# as14120_fpga_cypress.net
KiCad netlist of a schematic drawn in Altium Designer
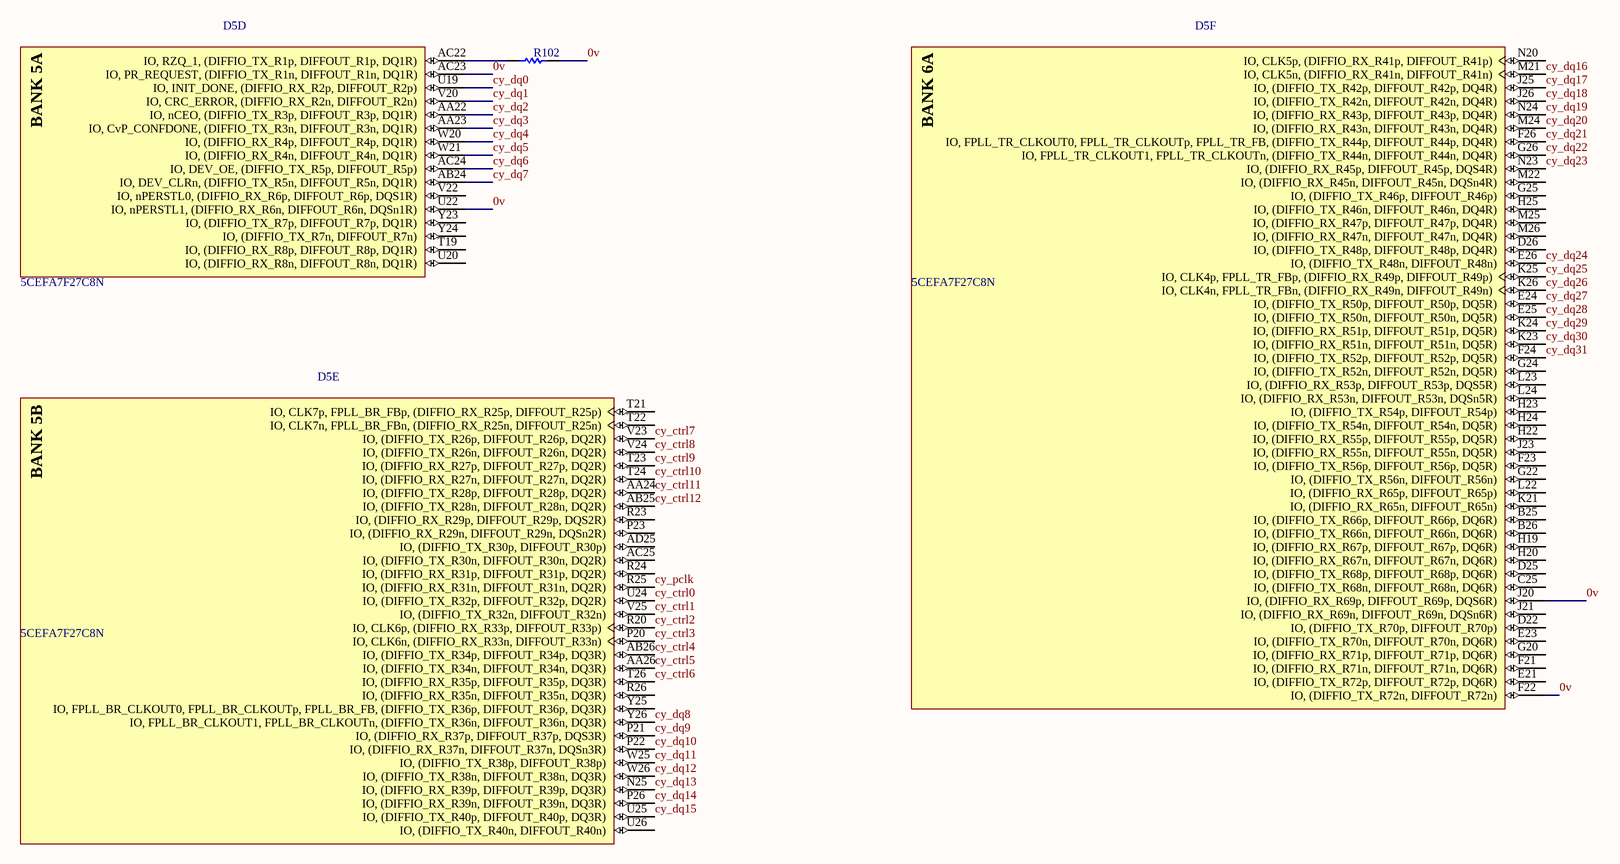
[diagram p0: as14120_fpga_cypress.SchDoc]

(export (version "E")
  (design (tool "Eeschema 10.0.6"))
  (components
    (comp (ref "D5")
      (value "5CEFA7F27C8N")
      (footprint "ALTR-672-FBGA-2000A")
      (fields (field (name "MANUFACTURER") "Altera"))
      (libsource (lib "Altera Cyclone V E") (part "5CEFA7F27C8N"))
    )
    (comp (ref "R102")
      (value "???")
      (footprint "RESC0603(1608)_L")
      (description "1K 0.1W 5% 0603 (1608 Metric)  SMD")
      (fields (field (name "TOLERANCE") "5 %") (field (name "POWER") "0.1 W"))
      (libsource (lib "as14120") (part "RES_0603"))
    )
  )
  (nets
    (net (code "1") (name "/0v") (class "Default")
      (node (ref "D5") (pin "AC23") (pinfunction "IO,_PR_REQUEST,_(DIFFIO_TX_R1n,_DIFFOUT_R1n,_DQ1R)_AC23") (pintype "bidirectional"))
      (node (ref "D5") (pin "F22") (pinfunction "IO,_(DIFFIO_TX_R72n,_DIFFOUT_R72n)_F22") (pintype "bidirectional"))
      (node (ref "D5") (pin "J20") (pinfunction "IO,_(DIFFIO_RX_R69p,_DIFFOUT_R69p,_DQS6R)_J20") (pintype "bidirectional"))
      (node (ref "D5") (pin "U22") (pinfunction "IO,_nPERSTL1,_(DIFFIO_RX_R6n,_DIFFOUT_R6n,_DQSn1R)_U22") (pintype "bidirectional"))
      (node (ref "R102") (pin "2") (pinfunction "2_2") (pintype "passive"))
    )
    (net (code "2") (name "/cy_ctrl0") (class "Default")
      (node (ref "D5") (pin "U24") (pinfunction "IO,_(DIFFIO_TX_R32p,_DIFFOUT_R32p,_DQ2R)_U24") (pintype "bidirectional"))
    )
    (net (code "3") (name "/cy_ctrl1") (class "Default")
      (node (ref "D5") (pin "V25") (pinfunction "IO,_(DIFFIO_TX_R32n,_DIFFOUT_R32n)_V25") (pintype "bidirectional"))
    )
    (net (code "4") (name "/cy_ctrl2") (class "Default")
      (node (ref "D5") (pin "R20") (pinfunction "IO,_CLK6p,_(DIFFIO_RX_R33p,_DIFFOUT_R33p)_R20") (pintype "bidirectional"))
    )
    (net (code "5") (name "/cy_ctrl3") (class "Default")
      (node (ref "D5") (pin "P20") (pinfunction "IO,_CLK6n,_(DIFFIO_RX_R33n,_DIFFOUT_R33n)_P20") (pintype "bidirectional"))
    )
    (net (code "6") (name "/cy_ctrl4") (class "Default")
      (node (ref "D5") (pin "AB26") (pinfunction "IO,_(DIFFIO_TX_R34p,_DIFFOUT_R34p,_DQ3R)_AB26") (pintype "bidirectional"))
    )
    (net (code "7") (name "/cy_ctrl5") (class "Default")
      (node (ref "D5") (pin "AA26") (pinfunction "IO,_(DIFFIO_TX_R34n,_DIFFOUT_R34n,_DQ3R)_AA26") (pintype "bidirectional"))
    )
    (net (code "8") (name "/cy_ctrl6") (class "Default")
      (node (ref "D5") (pin "T26") (pinfunction "IO,_(DIFFIO_RX_R35p,_DIFFOUT_R35p,_DQ3R)_T26") (pintype "bidirectional"))
    )
    (net (code "9") (name "/cy_ctrl7") (class "Default")
      (node (ref "D5") (pin "V23") (pinfunction "IO,_(DIFFIO_TX_R26p,_DIFFOUT_R26p,_DQ2R)_V23") (pintype "bidirectional"))
    )
    (net (code "10") (name "/cy_ctrl8") (class "Default")
      (node (ref "D5") (pin "V24") (pinfunction "IO,_(DIFFIO_TX_R26n,_DIFFOUT_R26n,_DQ2R)_V24") (pintype "bidirectional"))
    )
    (net (code "11") (name "/cy_ctrl9") (class "Default")
      (node (ref "D5") (pin "T23") (pinfunction "IO,_(DIFFIO_RX_R27p,_DIFFOUT_R27p,_DQ2R)_T23") (pintype "bidirectional"))
    )
    (net (code "12") (name "/cy_ctrl10") (class "Default")
      (node (ref "D5") (pin "T24") (pinfunction "IO,_(DIFFIO_RX_R27n,_DIFFOUT_R27n,_DQ2R)_T24") (pintype "bidirectional"))
    )
    (net (code "13") (name "/cy_ctrl11") (class "Default")
      (node (ref "D5") (pin "AA24") (pinfunction "IO,_(DIFFIO_TX_R28p,_DIFFOUT_R28p,_DQ2R)_AA24") (pintype "bidirectional"))
    )
    (net (code "14") (name "/cy_ctrl12") (class "Default")
      (node (ref "D5") (pin "AB25") (pinfunction "IO,_(DIFFIO_TX_R28n,_DIFFOUT_R28n,_DQ2R)_AB25") (pintype "bidirectional"))
    )
    (net (code "15") (name "/cy_dq0") (class "Default")
      (node (ref "D5") (pin "U19") (pinfunction "IO,_INIT_DONE,_(DIFFIO_RX_R2p,_DIFFOUT_R2p)_U19") (pintype "bidirectional"))
    )
    (net (code "16") (name "/cy_dq1") (class "Default")
      (node (ref "D5") (pin "V20") (pinfunction "IO,_CRC_ERROR,_(DIFFIO_RX_R2n,_DIFFOUT_R2n)_V20") (pintype "bidirectional"))
    )
    (net (code "17") (name "/cy_dq2") (class "Default")
      (node (ref "D5") (pin "AA22") (pinfunction "IO,_nCEO,_(DIFFIO_TX_R3p,_DIFFOUT_R3p,_DQ1R)_AA22") (pintype "bidirectional"))
    )
    (net (code "18") (name "/cy_dq3") (class "Default")
      (node (ref "D5") (pin "AA23") (pinfunction "IO,_CvP_CONFDONE,_(DIFFIO_TX_R3n,_DIFFOUT_R3n,_DQ1R)_AA23") (pintype "bidirectional"))
    )
    (net (code "19") (name "/cy_dq4") (class "Default")
      (node (ref "D5") (pin "W20") (pinfunction "IO,_(DIFFIO_RX_R4p,_DIFFOUT_R4p,_DQ1R)_W20") (pintype "bidirectional"))
    )
    (net (code "20") (name "/cy_dq5") (class "Default")
      (node (ref "D5") (pin "W21") (pinfunction "IO,_(DIFFIO_RX_R4n,_DIFFOUT_R4n,_DQ1R)_W21") (pintype "bidirectional"))
    )
    (net (code "21") (name "/cy_dq6") (class "Default")
      (node (ref "D5") (pin "AC24") (pinfunction "IO,_DEV_OE,_(DIFFIO_TX_R5p,_DIFFOUT_R5p)_AC24") (pintype "bidirectional"))
    )
    (net (code "22") (name "/cy_dq7") (class "Default")
      (node (ref "D5") (pin "AB24") (pinfunction "IO,_DEV_CLRn,_(DIFFIO_TX_R5n,_DIFFOUT_R5n,_DQ1R)_AB24") (pintype "bidirectional"))
    )
    (net (code "23") (name "/cy_dq8") (class "Default")
      (node (ref "D5") (pin "Y26") (pinfunction "IO,_FPLL_BR_CLKOUT1,_FPLL_BR_CLKOUTn,_(DIFFIO_TX_R36n,_DIFFOUT_R36n,_DQ3R)_Y26") (pintype "bidirectional"))
    )
    (net (code "24") (name "/cy_dq9") (class "Default")
      (node (ref "D5") (pin "P21") (pinfunction "IO,_(DIFFIO_RX_R37p,_DIFFOUT_R37p,_DQS3R)_P21") (pintype "bidirectional"))
    )
    (net (code "25") (name "/cy_dq10") (class "Default")
      (node (ref "D5") (pin "P22") (pinfunction "IO,_(DIFFIO_RX_R37n,_DIFFOUT_R37n,_DQSn3R)_P22") (pintype "bidirectional"))
    )
    (net (code "26") (name "/cy_dq11") (class "Default")
      (node (ref "D5") (pin "W25") (pinfunction "IO,_(DIFFIO_TX_R38p,_DIFFOUT_R38p)_W25") (pintype "bidirectional"))
    )
    (net (code "27") (name "/cy_dq12") (class "Default")
      (node (ref "D5") (pin "W26") (pinfunction "IO,_(DIFFIO_TX_R38n,_DIFFOUT_R38n,_DQ3R)_W26") (pintype "bidirectional"))
    )
    (net (code "28") (name "/cy_dq13") (class "Default")
      (node (ref "D5") (pin "N25") (pinfunction "IO,_(DIFFIO_RX_R39p,_DIFFOUT_R39p,_DQ3R)_N25") (pintype "bidirectional"))
    )
    (net (code "29") (name "/cy_dq14") (class "Default")
      (node (ref "D5") (pin "P26") (pinfunction "IO,_(DIFFIO_RX_R39n,_DIFFOUT_R39n,_DQ3R)_P26") (pintype "bidirectional"))
    )
    (net (code "30") (name "/cy_dq15") (class "Default")
      (node (ref "D5") (pin "U25") (pinfunction "IO,_(DIFFIO_TX_R40p,_DIFFOUT_R40p,_DQ3R)_U25") (pintype "bidirectional"))
    )
    (net (code "31") (name "/cy_dq16") (class "Default")
      (node (ref "D5") (pin "M21") (pinfunction "IO,_CLK5n,_(DIFFIO_RX_R41n,_DIFFOUT_R41n)_M21") (pintype "bidirectional"))
    )
    (net (code "32") (name "/cy_dq17") (class "Default")
      (node (ref "D5") (pin "J25") (pinfunction "IO,_(DIFFIO_TX_R42p,_DIFFOUT_R42p,_DQ4R)_J25") (pintype "bidirectional"))
    )
    (net (code "33") (name "/cy_dq18") (class "Default")
      (node (ref "D5") (pin "J26") (pinfunction "IO,_(DIFFIO_TX_R42n,_DIFFOUT_R42n,_DQ4R)_J26") (pintype "bidirectional"))
    )
    (net (code "34") (name "/cy_dq19") (class "Default")
      (node (ref "D5") (pin "N24") (pinfunction "IO,_(DIFFIO_RX_R43p,_DIFFOUT_R43p,_DQ4R)_N24") (pintype "bidirectional"))
    )
    (net (code "35") (name "/cy_dq20") (class "Default")
      (node (ref "D5") (pin "M24") (pinfunction "IO,_(DIFFIO_RX_R43n,_DIFFOUT_R43n,_DQ4R)_M24") (pintype "bidirectional"))
    )
    (net (code "36") (name "/cy_dq21") (class "Default")
      (node (ref "D5") (pin "F26") (pinfunction "IO,_FPLL_TR_CLKOUT0,_FPLL_TR_CLKOUTp,_FPLL_TR_FB,_(DIFFIO_TX_R44p,_DIFFOUT_R44p,_DQ4R)_F26") (pintype "bidirectional"))
    )
    (net (code "37") (name "/cy_dq22") (class "Default")
      (node (ref "D5") (pin "G26") (pinfunction "IO,_FPLL_TR_CLKOUT1,_FPLL_TR_CLKOUTn,_(DIFFIO_TX_R44n,_DIFFOUT_R44n,_DQ4R)_G26") (pintype "bidirectional"))
    )
    (net (code "38") (name "/cy_dq23") (class "Default")
      (node (ref "D5") (pin "N23") (pinfunction "IO,_(DIFFIO_RX_R45p,_DIFFOUT_R45p,_DQS4R)_N23") (pintype "bidirectional"))
    )
    (net (code "39") (name "/cy_dq24") (class "Default")
      (node (ref "D5") (pin "E26") (pinfunction "IO,_(DIFFIO_TX_R48n,_DIFFOUT_R48n)_E26") (pintype "bidirectional"))
    )
    (net (code "40") (name "/cy_dq25") (class "Default")
      (node (ref "D5") (pin "K25") (pinfunction "IO,_CLK4p,_FPLL_TR_FBp,_(DIFFIO_RX_R49p,_DIFFOUT_R49p)_K25") (pintype "bidirectional"))
    )
    (net (code "41") (name "/cy_dq26") (class "Default")
      (node (ref "D5") (pin "K26") (pinfunction "IO,_CLK4n,_FPLL_TR_FBn,_(DIFFIO_RX_R49n,_DIFFOUT_R49n)_K26") (pintype "bidirectional"))
    )
    (net (code "42") (name "/cy_dq27") (class "Default")
      (node (ref "D5") (pin "E24") (pinfunction "IO,_(DIFFIO_TX_R50p,_DIFFOUT_R50p,_DQ5R)_E24") (pintype "bidirectional"))
    )
    (net (code "43") (name "/cy_dq28") (class "Default")
      (node (ref "D5") (pin "E25") (pinfunction "IO,_(DIFFIO_TX_R50n,_DIFFOUT_R50n,_DQ5R)_E25") (pintype "bidirectional"))
    )
    (net (code "44") (name "/cy_dq29") (class "Default")
      (node (ref "D5") (pin "K24") (pinfunction "IO,_(DIFFIO_RX_R51p,_DIFFOUT_R51p,_DQ5R)_K24") (pintype "bidirectional"))
    )
    (net (code "45") (name "/cy_dq30") (class "Default")
      (node (ref "D5") (pin "K23") (pinfunction "IO,_(DIFFIO_RX_R51n,_DIFFOUT_R51n,_DQ5R)_K23") (pintype "bidirectional"))
    )
    (net (code "46") (name "/cy_dq31") (class "Default")
      (node (ref "D5") (pin "F24") (pinfunction "IO,_(DIFFIO_TX_R52p,_DIFFOUT_R52p,_DQ5R)_F24") (pintype "bidirectional"))
    )
    (net (code "47") (name "/cy_pclk") (class "Default")
      (node (ref "D5") (pin "R25") (pinfunction "IO,_(DIFFIO_RX_R31n,_DIFFOUT_R31n,_DQ2R)_R25") (pintype "bidirectional"))
    )
    (net (code "48") (name "Net-(D5D-IO,_RZQ_1,_(DIFFIO_TX_R1p,_DIFFOUT_R1p,_DQ1R))") (class "Default")
      (node (ref "D5") (pin "AC22") (pinfunction "IO,_RZQ_1,_(DIFFIO_TX_R1p,_DIFFOUT_R1p,_DQ1R)_AC22") (pintype "bidirectional"))
      (node (ref "R102") (pin "1") (pinfunction "1_1") (pintype "passive"))
    )
    (net (code "49") (name "unconnected-(D5D-IO,_(DIFFIO_RX_R8n,_DIFFOUT_R8n,_DQ1R)-PadU20)") (class "Default")
      (node (ref "D5") (pin "U20") (pinfunction "IO,_(DIFFIO_RX_R8n,_DIFFOUT_R8n,_DQ1R)_U20") (pintype "bidirectional"))
    )
    (net (code "50") (name "unconnected-(D5D-IO,_(DIFFIO_RX_R8p,_DIFFOUT_R8p,_DQ1R)-PadT19)") (class "Default")
      (node (ref "D5") (pin "T19") (pinfunction "IO,_(DIFFIO_RX_R8p,_DIFFOUT_R8p,_DQ1R)_T19") (pintype "bidirectional"))
    )
    (net (code "51") (name "unconnected-(D5D-IO,_(DIFFIO_TX_R7n,_DIFFOUT_R7n)-PadY24)") (class "Default")
      (node (ref "D5") (pin "Y24") (pinfunction "IO,_(DIFFIO_TX_R7n,_DIFFOUT_R7n)_Y24") (pintype "bidirectional"))
    )
    (net (code "52") (name "unconnected-(D5D-IO,_(DIFFIO_TX_R7p,_DIFFOUT_R7p,_DQ1R)-PadY23)") (class "Default")
      (node (ref "D5") (pin "Y23") (pinfunction "IO,_(DIFFIO_TX_R7p,_DIFFOUT_R7p,_DQ1R)_Y23") (pintype "bidirectional"))
    )
    (net (code "53") (name "unconnected-(D5D-IO,_nPERSTL0,_(DIFFIO_RX_R6p,_DIFFOUT_R6p,_DQS1R)-PadV22)") (class "Default")
      (node (ref "D5") (pin "V22") (pinfunction "IO,_nPERSTL0,_(DIFFIO_RX_R6p,_DIFFOUT_R6p,_DQS1R)_V22") (pintype "bidirectional"))
    )
    (net (code "54") (name "unconnected-(D5E-IO,_(DIFFIO_RX_R29n,_DIFFOUT_R29n,_DQSn2R)-PadP23)") (class "Default")
      (node (ref "D5") (pin "P23") (pinfunction "IO,_(DIFFIO_RX_R29n,_DIFFOUT_R29n,_DQSn2R)_P23") (pintype "bidirectional"))
    )
    (net (code "55") (name "unconnected-(D5E-IO,_(DIFFIO_RX_R29p,_DIFFOUT_R29p,_DQS2R)-PadR23)") (class "Default")
      (node (ref "D5") (pin "R23") (pinfunction "IO,_(DIFFIO_RX_R29p,_DIFFOUT_R29p,_DQS2R)_R23") (pintype "bidirectional"))
    )
    (net (code "56") (name "unconnected-(D5E-IO,_(DIFFIO_RX_R31p,_DIFFOUT_R31p,_DQ2R)-PadR24)") (class "Default")
      (node (ref "D5") (pin "R24") (pinfunction "IO,_(DIFFIO_RX_R31p,_DIFFOUT_R31p,_DQ2R)_R24") (pintype "bidirectional"))
    )
    (net (code "57") (name "unconnected-(D5E-IO,_(DIFFIO_RX_R35n,_DIFFOUT_R35n,_DQ3R)-PadR26)") (class "Default")
      (node (ref "D5") (pin "R26") (pinfunction "IO,_(DIFFIO_RX_R35n,_DIFFOUT_R35n,_DQ3R)_R26") (pintype "bidirectional"))
    )
    (net (code "58") (name "unconnected-(D5E-IO,_(DIFFIO_TX_R30n,_DIFFOUT_R30n,_DQ2R)-PadAC25)") (class "Default")
      (node (ref "D5") (pin "AC25") (pinfunction "IO,_(DIFFIO_TX_R30n,_DIFFOUT_R30n,_DQ2R)_AC25") (pintype "bidirectional"))
    )
    (net (code "59") (name "unconnected-(D5E-IO,_(DIFFIO_TX_R30p,_DIFFOUT_R30p)-PadAD25)") (class "Default")
      (node (ref "D5") (pin "AD25") (pinfunction "IO,_(DIFFIO_TX_R30p,_DIFFOUT_R30p)_AD25") (pintype "bidirectional"))
    )
    (net (code "60") (name "unconnected-(D5E-IO,_(DIFFIO_TX_R40n,_DIFFOUT_R40n)-PadU26)") (class "Default")
      (node (ref "D5") (pin "U26") (pinfunction "IO,_(DIFFIO_TX_R40n,_DIFFOUT_R40n)_U26") (pintype "bidirectional"))
    )
    (net (code "61") (name "unconnected-(D5E-IO,_CLK7n,_FPLL_BR_FBn,_(DIFFIO_RX_R25n,_DIFFOUT_R25n)-PadT22)") (class "Default")
      (node (ref "D5") (pin "T22") (pinfunction "IO,_CLK7n,_FPLL_BR_FBn,_(DIFFIO_RX_R25n,_DIFFOUT_R25n)_T22") (pintype "bidirectional"))
    )
    (net (code "62") (name "unconnected-(D5E-IO,_CLK7p,_FPLL_BR_FBp,_(DIFFIO_RX_R25p,_DIFFOUT_R25p)-PadT21)") (class "Default")
      (node (ref "D5") (pin "T21") (pinfunction "IO,_CLK7p,_FPLL_BR_FBp,_(DIFFIO_RX_R25p,_DIFFOUT_R25p)_T21") (pintype "bidirectional"))
    )
    (net (code "63") (name "unconnected-(D5E-IO,_FPLL_BR_CLKOUT0,_FPLL_BR_CLKOUTp,_FPLL_BR_FB,_(DIFFIO_TX_R36p,_DIFFOUT_R36p,_DQ3R)-PadY25)") (class "Default")
      (node (ref "D5") (pin "Y25") (pinfunction "IO,_FPLL_BR_CLKOUT0,_FPLL_BR_CLKOUTp,_FPLL_BR_FB,_(DIFFIO_TX_R36p,_DIFFOUT_R36p,_DQ3R)_Y25") (pintype "bidirectional"))
    )
    (net (code "64") (name "unconnected-(D5F-IO,_(DIFFIO_RX_R45n,_DIFFOUT_R45n,_DQSn4R)-PadM22)") (class "Default")
      (node (ref "D5") (pin "M22") (pinfunction "IO,_(DIFFIO_RX_R45n,_DIFFOUT_R45n,_DQSn4R)_M22") (pintype "bidirectional"))
    )
    (net (code "65") (name "unconnected-(D5F-IO,_(DIFFIO_RX_R47n,_DIFFOUT_R47n,_DQ4R)-PadM26)") (class "Default")
      (node (ref "D5") (pin "M26") (pinfunction "IO,_(DIFFIO_RX_R47n,_DIFFOUT_R47n,_DQ4R)_M26") (pintype "bidirectional"))
    )
    (net (code "66") (name "unconnected-(D5F-IO,_(DIFFIO_RX_R47p,_DIFFOUT_R47p,_DQ4R)-PadM25)") (class "Default")
      (node (ref "D5") (pin "M25") (pinfunction "IO,_(DIFFIO_RX_R47p,_DIFFOUT_R47p,_DQ4R)_M25") (pintype "bidirectional"))
    )
    (net (code "67") (name "unconnected-(D5F-IO,_(DIFFIO_RX_R53n,_DIFFOUT_R53n,_DQSn5R)-PadL24)") (class "Default")
      (node (ref "D5") (pin "L24") (pinfunction "IO,_(DIFFIO_RX_R53n,_DIFFOUT_R53n,_DQSn5R)_L24") (pintype "bidirectional"))
    )
    (net (code "68") (name "unconnected-(D5F-IO,_(DIFFIO_RX_R53p,_DIFFOUT_R53p,_DQS5R)-PadL23)") (class "Default")
      (node (ref "D5") (pin "L23") (pinfunction "IO,_(DIFFIO_RX_R53p,_DIFFOUT_R53p,_DQS5R)_L23") (pintype "bidirectional"))
    )
    (net (code "69") (name "unconnected-(D5F-IO,_(DIFFIO_RX_R55n,_DIFFOUT_R55n,_DQ5R)-PadJ23)") (class "Default")
      (node (ref "D5") (pin "J23") (pinfunction "IO,_(DIFFIO_RX_R55n,_DIFFOUT_R55n,_DQ5R)_J23") (pintype "bidirectional"))
    )
    (net (code "70") (name "unconnected-(D5F-IO,_(DIFFIO_RX_R55p,_DIFFOUT_R55p,_DQ5R)-PadH22)") (class "Default")
      (node (ref "D5") (pin "H22") (pinfunction "IO,_(DIFFIO_RX_R55p,_DIFFOUT_R55p,_DQ5R)_H22") (pintype "bidirectional"))
    )
    (net (code "71") (name "unconnected-(D5F-IO,_(DIFFIO_RX_R65n,_DIFFOUT_R65n)-PadK21)") (class "Default")
      (node (ref "D5") (pin "K21") (pinfunction "IO,_(DIFFIO_RX_R65n,_DIFFOUT_R65n)_K21") (pintype "bidirectional"))
    )
    (net (code "72") (name "unconnected-(D5F-IO,_(DIFFIO_RX_R65p,_DIFFOUT_R65p)-PadL22)") (class "Default")
      (node (ref "D5") (pin "L22") (pinfunction "IO,_(DIFFIO_RX_R65p,_DIFFOUT_R65p)_L22") (pintype "bidirectional"))
    )
    (net (code "73") (name "unconnected-(D5F-IO,_(DIFFIO_RX_R67n,_DIFFOUT_R67n,_DQ6R)-PadH20)") (class "Default")
      (node (ref "D5") (pin "H20") (pinfunction "IO,_(DIFFIO_RX_R67n,_DIFFOUT_R67n,_DQ6R)_H20") (pintype "bidirectional"))
    )
    (net (code "74") (name "unconnected-(D5F-IO,_(DIFFIO_RX_R67p,_DIFFOUT_R67p,_DQ6R)-PadH19)") (class "Default")
      (node (ref "D5") (pin "H19") (pinfunction "IO,_(DIFFIO_RX_R67p,_DIFFOUT_R67p,_DQ6R)_H19") (pintype "bidirectional"))
    )
    (net (code "75") (name "unconnected-(D5F-IO,_(DIFFIO_RX_R69n,_DIFFOUT_R69n,_DQSn6R)-PadJ21)") (class "Default")
      (node (ref "D5") (pin "J21") (pinfunction "IO,_(DIFFIO_RX_R69n,_DIFFOUT_R69n,_DQSn6R)_J21") (pintype "bidirectional"))
    )
    (net (code "76") (name "unconnected-(D5F-IO,_(DIFFIO_RX_R71n,_DIFFOUT_R71n,_DQ6R)-PadF21)") (class "Default")
      (node (ref "D5") (pin "F21") (pinfunction "IO,_(DIFFIO_RX_R71n,_DIFFOUT_R71n,_DQ6R)_F21") (pintype "bidirectional"))
    )
    (net (code "77") (name "unconnected-(D5F-IO,_(DIFFIO_RX_R71p,_DIFFOUT_R71p,_DQ6R)-PadG20)") (class "Default")
      (node (ref "D5") (pin "G20") (pinfunction "IO,_(DIFFIO_RX_R71p,_DIFFOUT_R71p,_DQ6R)_G20") (pintype "bidirectional"))
    )
    (net (code "78") (name "unconnected-(D5F-IO,_(DIFFIO_TX_R46n,_DIFFOUT_R46n,_DQ4R)-PadH25)") (class "Default")
      (node (ref "D5") (pin "H25") (pinfunction "IO,_(DIFFIO_TX_R46n,_DIFFOUT_R46n,_DQ4R)_H25") (pintype "bidirectional"))
    )
    (net (code "79") (name "unconnected-(D5F-IO,_(DIFFIO_TX_R46p,_DIFFOUT_R46p)-PadG25)") (class "Default")
      (node (ref "D5") (pin "G25") (pinfunction "IO,_(DIFFIO_TX_R46p,_DIFFOUT_R46p)_G25") (pintype "bidirectional"))
    )
    (net (code "80") (name "unconnected-(D5F-IO,_(DIFFIO_TX_R48p,_DIFFOUT_R48p,_DQ4R)-PadD26)") (class "Default")
      (node (ref "D5") (pin "D26") (pinfunction "IO,_(DIFFIO_TX_R48p,_DIFFOUT_R48p,_DQ4R)_D26") (pintype "bidirectional"))
    )
    (net (code "81") (name "unconnected-(D5F-IO,_(DIFFIO_TX_R52n,_DIFFOUT_R52n,_DQ5R)-PadG24)") (class "Default")
      (node (ref "D5") (pin "G24") (pinfunction "IO,_(DIFFIO_TX_R52n,_DIFFOUT_R52n,_DQ5R)_G24") (pintype "bidirectional"))
    )
    (net (code "82") (name "unconnected-(D5F-IO,_(DIFFIO_TX_R54n,_DIFFOUT_R54n,_DQ5R)-PadH24)") (class "Default")
      (node (ref "D5") (pin "H24") (pinfunction "IO,_(DIFFIO_TX_R54n,_DIFFOUT_R54n,_DQ5R)_H24") (pintype "bidirectional"))
    )
    (net (code "83") (name "unconnected-(D5F-IO,_(DIFFIO_TX_R54p,_DIFFOUT_R54p)-PadH23)") (class "Default")
      (node (ref "D5") (pin "H23") (pinfunction "IO,_(DIFFIO_TX_R54p,_DIFFOUT_R54p)_H23") (pintype "bidirectional"))
    )
    (net (code "84") (name "unconnected-(D5F-IO,_(DIFFIO_TX_R56n,_DIFFOUT_R56n)-PadG22)") (class "Default")
      (node (ref "D5") (pin "G22") (pinfunction "IO,_(DIFFIO_TX_R56n,_DIFFOUT_R56n)_G22") (pintype "bidirectional"))
    )
    (net (code "85") (name "unconnected-(D5F-IO,_(DIFFIO_TX_R56p,_DIFFOUT_R56p,_DQ5R)-PadF23)") (class "Default")
      (node (ref "D5") (pin "F23") (pinfunction "IO,_(DIFFIO_TX_R56p,_DIFFOUT_R56p,_DQ5R)_F23") (pintype "bidirectional"))
    )
    (net (code "86") (name "unconnected-(D5F-IO,_(DIFFIO_TX_R66n,_DIFFOUT_R66n,_DQ6R)-PadB26)") (class "Default")
      (node (ref "D5") (pin "B26") (pinfunction "IO,_(DIFFIO_TX_R66n,_DIFFOUT_R66n,_DQ6R)_B26") (pintype "bidirectional"))
    )
    (net (code "87") (name "unconnected-(D5F-IO,_(DIFFIO_TX_R66p,_DIFFOUT_R66p,_DQ6R)-PadB25)") (class "Default")
      (node (ref "D5") (pin "B25") (pinfunction "IO,_(DIFFIO_TX_R66p,_DIFFOUT_R66p,_DQ6R)_B25") (pintype "bidirectional"))
    )
    (net (code "88") (name "unconnected-(D5F-IO,_(DIFFIO_TX_R68n,_DIFFOUT_R68n,_DQ6R)-PadC25)") (class "Default")
      (node (ref "D5") (pin "C25") (pinfunction "IO,_(DIFFIO_TX_R68n,_DIFFOUT_R68n,_DQ6R)_C25") (pintype "bidirectional"))
    )
    (net (code "89") (name "unconnected-(D5F-IO,_(DIFFIO_TX_R68p,_DIFFOUT_R68p,_DQ6R)-PadD25)") (class "Default")
      (node (ref "D5") (pin "D25") (pinfunction "IO,_(DIFFIO_TX_R68p,_DIFFOUT_R68p,_DQ6R)_D25") (pintype "bidirectional"))
    )
    (net (code "90") (name "unconnected-(D5F-IO,_(DIFFIO_TX_R70n,_DIFFOUT_R70n,_DQ6R)-PadE23)") (class "Default")
      (node (ref "D5") (pin "E23") (pinfunction "IO,_(DIFFIO_TX_R70n,_DIFFOUT_R70n,_DQ6R)_E23") (pintype "bidirectional"))
    )
    (net (code "91") (name "unconnected-(D5F-IO,_(DIFFIO_TX_R70p,_DIFFOUT_R70p)-PadD22)") (class "Default")
      (node (ref "D5") (pin "D22") (pinfunction "IO,_(DIFFIO_TX_R70p,_DIFFOUT_R70p)_D22") (pintype "bidirectional"))
    )
    (net (code "92") (name "unconnected-(D5F-IO,_(DIFFIO_TX_R72p,_DIFFOUT_R72p,_DQ6R)-PadE21)") (class "Default")
      (node (ref "D5") (pin "E21") (pinfunction "IO,_(DIFFIO_TX_R72p,_DIFFOUT_R72p,_DQ6R)_E21") (pintype "bidirectional"))
    )
    (net (code "93") (name "unconnected-(D5F-IO,_CLK5p,_(DIFFIO_RX_R41p,_DIFFOUT_R41p)-PadN20)") (class "Default")
      (node (ref "D5") (pin "N20") (pinfunction "IO,_CLK5p,_(DIFFIO_RX_R41p,_DIFFOUT_R41p)_N20") (pintype "bidirectional"))
    )
  )
)
